# E-43_Inertial_sensor.net
KiCad netlist of a schematic drawn in Altium Designer
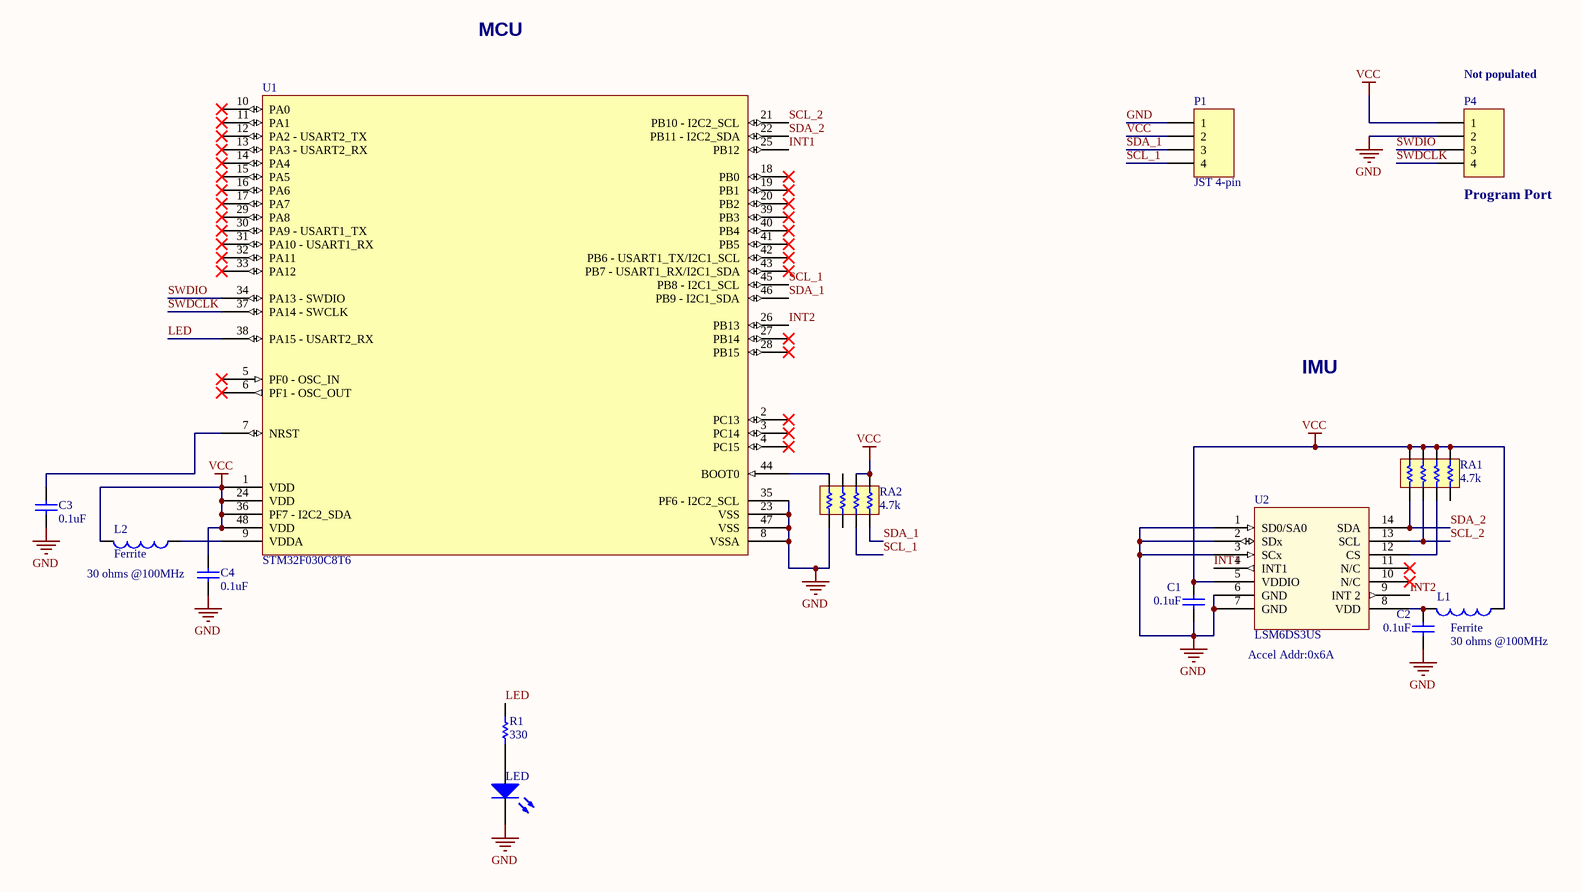
[diagram p0: E-43 Inertial sensor.SchDoc]

(export (version "E")
  (design (tool "Eeschema 10.0.6"))
  (components
    (comp (ref "C1")
      (value "0.1uF")
      (footprint "0603 TIGHT")
      (description "Capacitor")
      (fields (field (name "PUBLISHER") "Altium Limited"))
      (libsource (lib "SB_Discrete") (part "Cap"))
    )
    (comp (ref "C2")
      (value "0.1uF")
      (footprint "0603 TIGHT")
      (description "Capacitor")
      (fields (field (name "PUBLISHER") "Altium Limited"))
      (libsource (lib "SB_Discrete") (part "Cap"))
    )
    (comp (ref "C3")
      (value "0.1uF")
      (footprint "0603 TIGHT")
      (description "Capacitor")
      (fields (field (name "Comment") "Cap") (field (name "PUBLISHER") "Altium Limited"))
      (libsource (lib "SB_Discrete") (part "Cap"))
    )
    (comp (ref "C4")
      (value "0.1uF")
      (footprint "0603 TIGHT")
      (description "Capacitor")
      (fields (field (name "Comment") "Cap") (field (name "PUBLISHER") "Altium Limited"))
      (libsource (lib "SB_Discrete") (part "Cap"))
    )
    (comp (ref "L1")
      (value "Ferrite")
      (footprint "0603 TIGHT")
      (description "Inductor")
      (fields (field (name "ALTIUM_VALUE") "30 ohms @100MHz") (field (name "PUBLISHER") "Altium Limited"))
      (libsource (lib "Miscellaneous Devices") (part "Inductor"))
    )
    (comp (ref "L2")
      (value "Ferrite")
      (footprint "0603 TIGHT")
      (description "Inductor")
      (fields (field (name "ALTIUM_VALUE") "30 ohms @100MHz") (field (name "PUBLISHER") "Altium Limited"))
      (libsource (lib "Miscellaneous Devices") (part "Inductor"))
    )
    (comp (ref "LED")
      (value "LED2")
      (footprint "0805 LED - TIGHT")
      (description "Typical RED GaAs LED")
      (fields (field (name "PUBLISHER") "Altium Limited"))
      (libsource (lib "SB_Discrete") (part "LED1"))
    )
    (comp (ref "P1")
      (value "JST 4-pin")
      (footprint "JST-PH 4-pin SMD")
      (description "Header, 4-Pin")
      (fields (field (name "PUBLISHER") "Altium Limited"))
      (libsource (lib "Miscellaneous Connectors") (part "Header 4"))
    )
    (comp (ref "P4")
      (value "Not populated")
      (footprint "MINI PROG4")
      (description "Header, 4-Pin")
      (fields (field (name "PUBLISHER") "Altium Limited"))
      (libsource (lib "Miscellaneous Connectors") (part "Header 4"))
    )
    (comp (ref "R1")
      (value "330")
      (footprint "0603 tight")
      (description "Resistor")
      (fields (field (name "Comment") "Res1") (field (name "PUBLISHER") "Altium Limited"))
      (libsource (lib "SB_Discrete") (part "Res1"))
    )
    (comp (ref "RA1")
      (value "4.7k")
      (footprint "Resistor Array 4")
      (libsource (lib "") (part "Resistor Array 4_1"))
    )
    (comp (ref "RA2")
      (value "4.7k")
      (footprint "Resistor Array 4")
      (libsource (lib "SB_Discrete") (part "Resistor Array 4"))
    )
    (comp (ref "U1")
      (value "STM32F030C8T6")
      (footprint "LQFP48_M")
      (libsource (lib "ST Microcontroller 32-Bit STM32") (part "STM32F030C8"))
    )
    (comp (ref "U2")
      (value "LSM6DS3US")
      (footprint "LSM6DS3US")
      (libsource (lib "SB_Engineered_Components") (part "LSM6DS3US"))
    )
  )
  (nets
    (net (code "1") (name "/INT1") (class "Default")
      (node (ref "U1") (pin "25") (pinfunction "PB12_25") (pintype "bidirectional"))
      (node (ref "U2") (pin "4") (pinfunction "INT1_4") (pintype "output"))
    )
    (net (code "2") (name "/INT2") (class "Default")
      (node (ref "U1") (pin "26") (pinfunction "PB13_26") (pintype "bidirectional"))
      (node (ref "U2") (pin "9") (pinfunction "INT_2_9") (pintype "output"))
    )
    (net (code "3") (name "/LED") (class "Default")
      (node (ref "R1") (pin "2") (pinfunction "2_2") (pintype "passive"))
      (node (ref "U1") (pin "38") (pinfunction "PA15_-_USART2_RX_38") (pintype "bidirectional"))
    )
    (net (code "4") (name "/SCL_1") (class "Default")
      (node (ref "P1") (pin "4") (pinfunction "4_4") (pintype "passive"))
      (node (ref "RA2") (pin "5") (pinfunction "3_5") (pintype "passive"))
      (node (ref "U1") (pin "45") (pinfunction "PB8_-_I2C1_SCL_45") (pintype "bidirectional"))
    )
    (net (code "5") (name "/SCL_2") (class "Default")
      (node (ref "RA1") (pin "5") (pinfunction "3_5") (pintype "passive"))
      (node (ref "U1") (pin "21") (pinfunction "PB10_-_I2C2_SCL_21") (pintype "bidirectional"))
      (node (ref "U2") (pin "13") (pinfunction "SCL_13") (pintype "power_in"))
    )
    (net (code "6") (name "/SDA_1") (class "Default")
      (node (ref "P1") (pin "3") (pinfunction "3_3") (pintype "passive"))
      (node (ref "RA2") (pin "7") (pinfunction "7_7") (pintype "passive"))
      (node (ref "U1") (pin "46") (pinfunction "PB9_-_I2C1_SDA_46") (pintype "bidirectional"))
    )
    (net (code "7") (name "/SDA_2") (class "Default")
      (node (ref "RA1") (pin "7") (pinfunction "7_7") (pintype "passive"))
      (node (ref "U1") (pin "22") (pinfunction "PB11_-_I2C2_SDA_22") (pintype "bidirectional"))
      (node (ref "U2") (pin "14") (pinfunction "SDA_14") (pintype "power_in"))
    )
    (net (code "8") (name "/SWDCLK") (class "Default")
      (node (ref "P4") (pin "4") (pinfunction "4_4") (pintype "passive"))
      (node (ref "U1") (pin "37") (pinfunction "PA14_-_SWCLK_37") (pintype "bidirectional"))
    )
    (net (code "9") (name "/SWDIO") (class "Default")
      (node (ref "P4") (pin "3") (pinfunction "3_3") (pintype "passive"))
      (node (ref "U1") (pin "34") (pinfunction "PA13_-_SWDIO_34") (pintype "bidirectional"))
    )
    (net (code "10") (name "GND") (class "Default")
      (node (ref "C1") (pin "1") (pinfunction "1_1") (pintype "passive"))
      (node (ref "C2") (pin "1") (pinfunction "1_1") (pintype "passive"))
      (node (ref "C3") (pin "2") (pinfunction "2_2") (pintype "passive"))
      (node (ref "C4") (pin "2") (pinfunction "2_2") (pintype "passive"))
      (node (ref "LED") (pin "2") (pinfunction "K_2") (pintype "passive"))
      (node (ref "P1") (pin "1") (pinfunction "1_1") (pintype "passive"))
      (node (ref "P4") (pin "2") (pinfunction "2_2") (pintype "passive"))
      (node (ref "RA2") (pin "1") (pinfunction "1_1") (pintype "passive"))
      (node (ref "U1") (pin "23") (pinfunction "VSS_23") (pintype "power_in"))
      (node (ref "U1") (pin "35") (pinfunction "PF6_-_I2C2_SCL_35") (pintype "power_in"))
      (node (ref "U1") (pin "47") (pinfunction "VSS_47") (pintype "power_in"))
      (node (ref "U1") (pin "8") (pinfunction "VSSA_8") (pintype "power_in"))
      (node (ref "U2") (pin "1") (pinfunction "SD0/SA0_1") (pintype "input"))
      (node (ref "U2") (pin "2") (pinfunction "SDx_2") (pintype "bidirectional"))
      (node (ref "U2") (pin "3") (pinfunction "SCx_3") (pintype "input"))
      (node (ref "U2") (pin "6") (pinfunction "GND_6") (pintype "power_in"))
      (node (ref "U2") (pin "7") (pinfunction "GND_7") (pintype "power_in"))
    )
    (net (code "11") (name "Net-(LED-A)") (class "Default")
      (node (ref "LED") (pin "1") (pinfunction "A_1") (pintype "passive"))
      (node (ref "R1") (pin "1") (pinfunction "1_1") (pintype "passive"))
    )
    (net (code "12") (name "Net-(RA1-5)") (class "Default")
      (node (ref "RA1") (pin "3") (pinfunction "5_3") (pintype "passive"))
      (node (ref "U2") (pin "12") (pinfunction "CS_12") (pintype "power_in"))
    )
    (net (code "13") (name "Net-(U1-BOOT0)") (class "Default")
      (node (ref "RA2") (pin "2") (pinfunction "2_2") (pintype "passive"))
      (node (ref "U1") (pin "44") (pinfunction "BOOT0_44") (pintype "input"))
    )
    (net (code "14") (name "Net-(U1-NRST)") (class "Default")
      (node (ref "C3") (pin "1") (pinfunction "1_1") (pintype "passive"))
      (node (ref "U1") (pin "7") (pinfunction "NRST_7") (pintype "bidirectional"))
    )
    (net (code "15") (name "Net-(U1-VDDA)") (class "Default")
      (node (ref "L2") (pin "1") (pinfunction "1_1") (pintype "passive"))
      (node (ref "U1") (pin "9") (pinfunction "VDDA_9") (pintype "power_in"))
    )
    (net (code "16") (name "Net-(U2-VDD)") (class "Default")
      (node (ref "C2") (pin "2") (pinfunction "2_2") (pintype "passive"))
      (node (ref "L1") (pin "2") (pinfunction "2_2") (pintype "passive"))
      (node (ref "U2") (pin "8") (pinfunction "VDD_8") (pintype "power_in"))
    )
    (net (code "17") (name "VCC") (class "Default")
      (node (ref "C1") (pin "2") (pinfunction "2_2") (pintype "passive"))
      (node (ref "C4") (pin "1") (pinfunction "1_1") (pintype "passive"))
      (node (ref "L1") (pin "1") (pinfunction "1_1") (pintype "passive"))
      (node (ref "L2") (pin "2") (pinfunction "2_2") (pintype "passive"))
      (node (ref "P1") (pin "2") (pinfunction "2_2") (pintype "passive"))
      (node (ref "P4") (pin "1") (pinfunction "1_1") (pintype "passive"))
      (node (ref "RA1") (pin "2") (pinfunction "2_2") (pintype "passive"))
      (node (ref "RA1") (pin "4") (pinfunction "6_4") (pintype "passive"))
      (node (ref "RA1") (pin "6") (pinfunction "4_6") (pintype "passive"))
      (node (ref "RA1") (pin "8") (pinfunction "8_8") (pintype "passive"))
      (node (ref "RA2") (pin "6") (pinfunction "4_6") (pintype "passive"))
      (node (ref "RA2") (pin "8") (pinfunction "8_8") (pintype "passive"))
      (node (ref "U1") (pin "1") (pinfunction "VDD_1") (pintype "power_in"))
      (node (ref "U1") (pin "24") (pinfunction "VDD_24") (pintype "power_in"))
      (node (ref "U1") (pin "36") (pinfunction "PF7_-_I2C2_SDA_36") (pintype "power_in"))
      (node (ref "U1") (pin "48") (pinfunction "VDD_48") (pintype "power_in"))
      (node (ref "U2") (pin "5") (pinfunction "VDDIO_5") (pintype "power_in"))
    )
    (net (code "18") (name "unconnected-(RA1-Pad1)") (class "Default")
      (node (ref "RA1") (pin "1") (pinfunction "1_1") (pintype "passive"))
    )
    (net (code "19") (name "unconnected-(RA2-5-Pad3)") (class "Default")
      (node (ref "RA2") (pin "3") (pinfunction "5_3") (pintype "passive"))
    )
    (net (code "20") (name "unconnected-(RA2-6-Pad4)") (class "Default")
      (node (ref "RA2") (pin "4") (pinfunction "6_4") (pintype "passive"))
    )
    (net (code "21") (name "unconnected-(U1-PA0-Pad10)") (class "Default")
      (node (ref "U1") (pin "10") (pinfunction "PA0_10") (pintype "bidirectional+no_connect"))
    )
    (net (code "22") (name "unconnected-(U1-PA1-Pad11)") (class "Default")
      (node (ref "U1") (pin "11") (pinfunction "PA1_11") (pintype "bidirectional+no_connect"))
    )
    (net (code "23") (name "unconnected-(U1-PA2_-_USART2_TX-Pad12)") (class "Default")
      (node (ref "U1") (pin "12") (pinfunction "PA2_-_USART2_TX_12") (pintype "bidirectional+no_connect"))
    )
    (net (code "24") (name "unconnected-(U1-PA3_-_USART2_RX-Pad13)") (class "Default")
      (node (ref "U1") (pin "13") (pinfunction "PA3_-_USART2_RX_13") (pintype "bidirectional+no_connect"))
    )
    (net (code "25") (name "unconnected-(U1-PA4-Pad14)") (class "Default")
      (node (ref "U1") (pin "14") (pinfunction "PA4_14") (pintype "bidirectional+no_connect"))
    )
    (net (code "26") (name "unconnected-(U1-PA5-Pad15)") (class "Default")
      (node (ref "U1") (pin "15") (pinfunction "PA5_15") (pintype "bidirectional+no_connect"))
    )
    (net (code "27") (name "unconnected-(U1-PA6-Pad16)") (class "Default")
      (node (ref "U1") (pin "16") (pinfunction "PA6_16") (pintype "bidirectional+no_connect"))
    )
    (net (code "28") (name "unconnected-(U1-PA7-Pad17)") (class "Default")
      (node (ref "U1") (pin "17") (pinfunction "PA7_17") (pintype "bidirectional+no_connect"))
    )
    (net (code "29") (name "unconnected-(U1-PA8-Pad29)") (class "Default")
      (node (ref "U1") (pin "29") (pinfunction "PA8_29") (pintype "bidirectional+no_connect"))
    )
    (net (code "30") (name "unconnected-(U1-PA9_-_USART1_TX-Pad30)") (class "Default")
      (node (ref "U1") (pin "30") (pinfunction "PA9_-_USART1_TX_30") (pintype "bidirectional+no_connect"))
    )
    (net (code "31") (name "unconnected-(U1-PA10_-_USART1_RX-Pad31)") (class "Default")
      (node (ref "U1") (pin "31") (pinfunction "PA10_-_USART1_RX_31") (pintype "bidirectional+no_connect"))
    )
    (net (code "32") (name "unconnected-(U1-PA11-Pad32)") (class "Default")
      (node (ref "U1") (pin "32") (pinfunction "PA11_32") (pintype "bidirectional+no_connect"))
    )
    (net (code "33") (name "unconnected-(U1-PA12-Pad33)") (class "Default")
      (node (ref "U1") (pin "33") (pinfunction "PA12_33") (pintype "bidirectional+no_connect"))
    )
    (net (code "34") (name "unconnected-(U1-PB0-Pad18)") (class "Default")
      (node (ref "U1") (pin "18") (pinfunction "PB0_18") (pintype "bidirectional+no_connect"))
    )
    (net (code "35") (name "unconnected-(U1-PB1-Pad19)") (class "Default")
      (node (ref "U1") (pin "19") (pinfunction "PB1_19") (pintype "bidirectional+no_connect"))
    )
    (net (code "36") (name "unconnected-(U1-PB2-Pad20)") (class "Default")
      (node (ref "U1") (pin "20") (pinfunction "PB2_20") (pintype "bidirectional+no_connect"))
    )
    (net (code "37") (name "unconnected-(U1-PB3-Pad39)") (class "Default")
      (node (ref "U1") (pin "39") (pinfunction "PB3_39") (pintype "bidirectional+no_connect"))
    )
    (net (code "38") (name "unconnected-(U1-PB4-Pad40)") (class "Default")
      (node (ref "U1") (pin "40") (pinfunction "PB4_40") (pintype "bidirectional+no_connect"))
    )
    (net (code "39") (name "unconnected-(U1-PB5-Pad41)") (class "Default")
      (node (ref "U1") (pin "41") (pinfunction "PB5_41") (pintype "bidirectional+no_connect"))
    )
    (net (code "40") (name "unconnected-(U1-PB6_-_USART1_TX{slash}I2C1_SCL-Pad42)") (class "Default")
      (node (ref "U1") (pin "42") (pinfunction "PB6_-_USART1_TX/I2C1_SCL_42") (pintype "bidirectional+no_connect"))
    )
    (net (code "41") (name "unconnected-(U1-PB7_-_USART1_RX{slash}I2C1_SDA-Pad43)") (class "Default")
      (node (ref "U1") (pin "43") (pinfunction "PB7_-_USART1_RX/I2C1_SDA_43") (pintype "bidirectional+no_connect"))
    )
    (net (code "42") (name "unconnected-(U1-PB14-Pad27)") (class "Default")
      (node (ref "U1") (pin "27") (pinfunction "PB14_27") (pintype "bidirectional+no_connect"))
    )
    (net (code "43") (name "unconnected-(U1-PB15-Pad28)") (class "Default")
      (node (ref "U1") (pin "28") (pinfunction "PB15_28") (pintype "bidirectional+no_connect"))
    )
    (net (code "44") (name "unconnected-(U1-PC13-Pad2)") (class "Default")
      (node (ref "U1") (pin "2") (pinfunction "PC13_2") (pintype "bidirectional+no_connect"))
    )
    (net (code "45") (name "unconnected-(U1-PC14-Pad3)") (class "Default")
      (node (ref "U1") (pin "3") (pinfunction "PC14_3") (pintype "bidirectional+no_connect"))
    )
    (net (code "46") (name "unconnected-(U1-PC15-Pad4)") (class "Default")
      (node (ref "U1") (pin "4") (pinfunction "PC15_4") (pintype "bidirectional+no_connect"))
    )
    (net (code "47") (name "unconnected-(U1-PF0_-_OSC_IN-Pad5)") (class "Default")
      (node (ref "U1") (pin "5") (pinfunction "PF0_-_OSC_IN_5") (pintype "input+no_connect"))
    )
    (net (code "48") (name "unconnected-(U1-PF1_-_OSC_OUT-Pad6)") (class "Default")
      (node (ref "U1") (pin "6") (pinfunction "PF1_-_OSC_OUT_6") (pintype "output+no_connect"))
    )
    (net (code "49") (name "unconnected-(U2-N{slash}C-Pad10)") (class "Default")
      (node (ref "U2") (pin "10") (pinfunction "N/C_10") (pintype "tri_state+no_connect"))
    )
    (net (code "50") (name "unconnected-(U2-N{slash}C-Pad11)") (class "Default")
      (node (ref "U2") (pin "11") (pinfunction "N/C_11") (pintype "tri_state+no_connect"))
    )
  )
)
